# esp-01_board.net
KiCad netlist of a schematic drawn in EAGLE
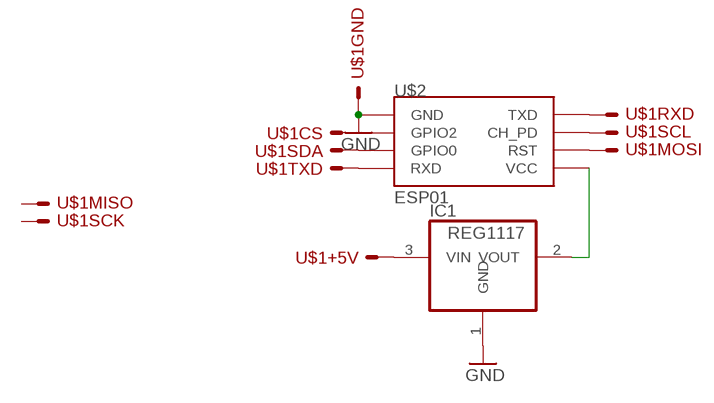
[diagram p0: schematic, sheet 1]

(export (version "E")
  (design (tool "Eeschema 10.0.6"))
  (components
    (comp (ref "IC1")
      (value "REG1117")
      (footprint "eagle-import:SOT223")
      (libsource (lib "eagle-import") (part "REG1117"))
    )
    (comp (ref "U$1")
      (value "SPI_BUS")
      (footprint "eagle-import:SPI_BUS")
      (libsource (lib "eagle-import") (part "SPI_BUS"))
    )
    (comp (ref "U$2")
      (value "ESP01")
      (footprint "eagle-import:ESP01")
      (libsource (lib "eagle-import") (part "ESP01"))
    )
  )
  (nets
    (net (code "1") (name "GND") (class "Default")
      (node (ref "IC1") (pin "1") (pinfunction "GND_1") (pintype "power_in"))
      (node (ref "U$1") (pin "GND") (pinfunction "S_GND") (pintype "passive"))
      (node (ref "U$2") (pin "GND") (pinfunction "GND_GND") (pintype "bidirectional"))
    )
    (net (code "2") (name "Net-(IC1-VIN)") (class "Default")
      (node (ref "IC1") (pin "3") (pinfunction "VIN_3") (pintype "input"))
      (node (ref "U$1") (pin "+5V") (pinfunction "S_+5V") (pintype "passive"))
    )
    (net (code "3") (name "Net-(IC1-VOUT)") (class "Default")
      (node (ref "IC1") (pin "2") (pinfunction "VOUT_2") (pintype "output"))
      (node (ref "U$2") (pin "VCC") (pinfunction "VCC_VCC") (pintype "bidirectional"))
    )
    (net (code "4") (name "Net-(U$1B-S)") (class "Default")
      (node (ref "U$1") (pin "CS") (pinfunction "S_CS") (pintype "passive"))
      (node (ref "U$2") (pin "GPIO2") (pinfunction "GPIO2_GPIO2") (pintype "bidirectional"))
    )
    (net (code "5") (name "Net-(U$1E-S)") (class "Default")
      (node (ref "U$1") (pin "MOSI") (pinfunction "S_MOSI") (pintype "passive"))
      (node (ref "U$2") (pin "RST") (pinfunction "RST_RST") (pintype "bidirectional"))
    )
    (net (code "6") (name "Net-(U$1F-S)") (class "Default")
      (node (ref "U$1") (pin "RXD") (pinfunction "S_RXD") (pintype "passive"))
      (node (ref "U$2") (pin "TX") (pinfunction "TXD_TX") (pintype "bidirectional"))
    )
    (net (code "7") (name "Net-(U$1H-S)") (class "Default")
      (node (ref "U$1") (pin "SCL") (pinfunction "S_SCL") (pintype "passive"))
      (node (ref "U$2") (pin "CH_PD") (pinfunction "CH_PD_CH_PD") (pintype "bidirectional"))
    )
    (net (code "8") (name "Net-(U$1I-S)") (class "Default")
      (node (ref "U$1") (pin "SDA") (pinfunction "S_SDA") (pintype "passive"))
      (node (ref "U$2") (pin "GPIO0") (pinfunction "GPIO0_GPIO0") (pintype "bidirectional"))
    )
    (net (code "9") (name "Net-(U$1J-S)") (class "Default")
      (node (ref "U$1") (pin "TXD") (pinfunction "S_TXD") (pintype "passive"))
      (node (ref "U$2") (pin "RX") (pinfunction "RXD_RX") (pintype "bidirectional"))
    )
    (net (code "10") (name "unconnected-(U$1D-S-PadMISO)") (class "Default")
      (node (ref "U$1") (pin "MISO") (pinfunction "S_MISO") (pintype "passive"))
    )
    (net (code "11") (name "unconnected-(U$1G-S-PadSCK)") (class "Default")
      (node (ref "U$1") (pin "SCK") (pinfunction "S_SCK") (pintype "passive"))
    )
  )
)
